# PowerSupply.net
KiCad netlist of a schematic drawn in Altium Designer
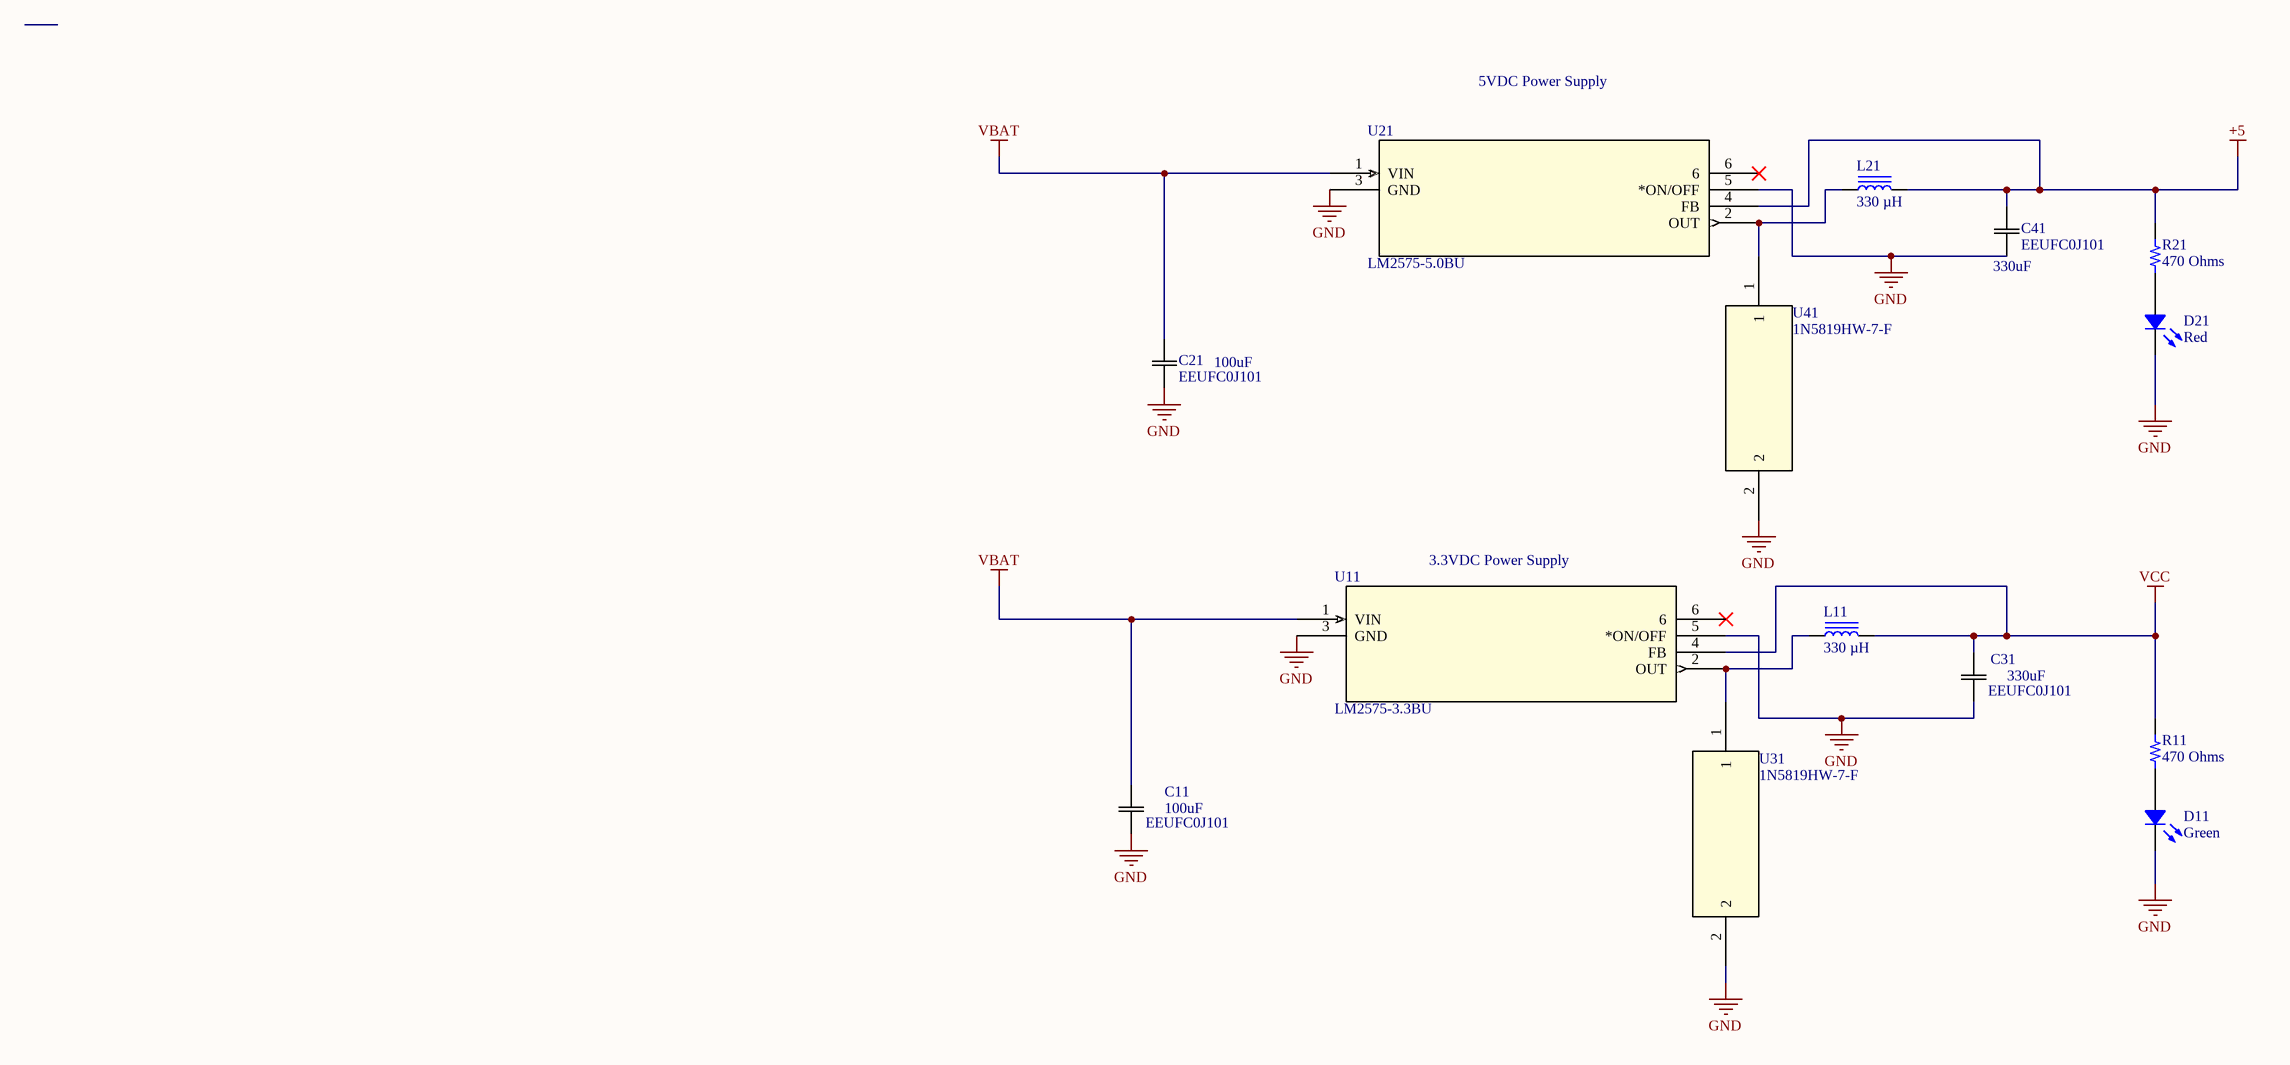
[diagram p0: PowerSupply.SchDoc]

(export (version "E")
  (design (tool "Eeschema 10.0.6"))
  (components
    (comp (ref "C11")
      (value "EEUFC0J101")
      (footprint "CAP_5 X 11_PAN")
      (description "No Description Available")
      (fields (field (name "ALTIUM_VALUE") "100uF"))
      (libsource (lib "EEUFC0J101") (part "EEUFC0J101"))
    )
    (comp (ref "C21")
      (value "EEUFC0J101")
      (footprint "CAP_5 X 11_PAN")
      (description "No Description Available")
      (fields (field (name "ALTIUM_VALUE") "100uF"))
      (libsource (lib "EEUFC0J101") (part "EEUFC0J101"))
    )
    (comp (ref "C31")
      (value "EEUFC0J101")
      (footprint "CAP_5 X 11_PAN")
      (description "No Description Available")
      (fields (field (name "ALTIUM_VALUE") "330uF"))
      (libsource (lib "EEUFC0J101") (part "EEUFC0J101"))
    )
    (comp (ref "C41")
      (value "EEUFC0J101")
      (footprint "CAP_5 X 11_PAN")
      (description "No Description Available")
      (fields (field (name "ALTIUM_VALUE") "330uF"))
      (libsource (lib "EEUFC0J101") (part "EEUFC0J101"))
    )
    (comp (ref "D11")
      (value "Green")
      (footprint "LED 1206_3216 GREEN")
      (description "LED GREEN 1206 SMD")
      (fields (field (name "PART NUMBER") "597-6322-107F") (field (name "MANUFACTURER") "Dialight"))
      (libsource (lib "Celestial Altium Library - altium_library") (part "LED"))
    )
    (comp (ref "D21")
      (value "Red")
      (footprint "LED 1206_3216 RED")
      (description "LED RED CLEAR 1206 SMD")
      (fields
        (field (name "PART NUMBER") "25-21/R6C-BR2S2B/2A")
        (field (name "MANUFACTURER") "Everlight Electronics Co Ltd")
      )
      (libsource (lib "Celestial Altium Library - altium_library") (part "LED"))
    )
    (comp (ref "L11")
      (value "330 µH")
      (footprint "BOURNS SRR1280")
      (description "FIXED IND 330UH 1.1A 600MOHM SMD")
      (fields (field (name "PART NUMBER") "SRR1280-331K") (field (name "MANUFACTURER") "Bourns Inc."))
      (libsource (lib "Celestial Altium Library - altium_library") (part "Inductor"))
    )
    (comp (ref "L21")
      (value "330 µH")
      (footprint "BOURNS SRR1280")
      (description "FIXED IND 330UH 1.1A 600MOHM SMD")
      (fields (field (name "PART NUMBER") "SRR1280-331K") (field (name "MANUFACTURER") "Bourns Inc."))
      (libsource (lib "Celestial Altium Library - altium_library") (part "Inductor"))
    )
    (comp (ref "R11")
      (value "470 Ohms")
      (footprint "RES 0805_2012")
      (description "RES 470 OHM 1% 1/4W 0805")
      (fields (field (name "PART NUMBER") "AC0805FR-7W470RL") (field (name "MANUFACTURER") "Yageo"))
      (libsource (lib "Celestial Altium Library - altium_library") (part "Resistor"))
    )
    (comp (ref "R21")
      (value "470 Ohms")
      (footprint "RES 0805_2012")
      (description "RES 470 OHM 1% 1/4W 0805")
      (fields (field (name "PART NUMBER") "AC0805FR-7W470RL") (field (name "MANUFACTURER") "Yageo"))
      (libsource (lib "Celestial Altium Library - altium_library") (part "Resistor"))
    )
    (comp (ref "U11")
      (value "LM2575-3.3BU")
      (footprint "TO-263-5_MCL")
      (description "No Description Available")
      (libsource (lib "LM2575-3P3BU") (part "LM2575-3.3BU"))
    )
    (comp (ref "U21")
      (value "LM2575-5.0BU")
      (footprint "TO-263-5_MCL-M")
      (description "No Description Available")
      (libsource (lib "LM2575-5P0BU") (part "LM2575-5.0BU"))
    )
    (comp (ref "U31")
      (value "1N5819HW-7-F")
      (footprint "1N5819HW-7-F_DIO")
      (description "No Description Available")
      (libsource (lib "1N5819HW-7-F") (part "1N5819HW-7-F"))
    )
    (comp (ref "U41")
      (value "1N5819HW-7-F")
      (footprint "1N5819HW-7-F_DIO")
      (description "No Description Available")
      (libsource (lib "1N5819HW-7-F") (part "1N5819HW-7-F"))
    )
  )
  (nets
    (net (code "1") (name "+5") (class "Default")
      (node (ref "C41") (pin "1") (pinfunction "1_1") (pintype "passive"))
      (node (ref "L21") (pin "2") (pinfunction "2_2") (pintype "passive"))
      (node (ref "R21") (pin "2") (pinfunction "2_2") (pintype "passive"))
      (node (ref "U21") (pin "4") (pinfunction "FB_4") (pintype "passive"))
    )
    (net (code "2") (name "GND") (class "Default")
      (node (ref "C11") (pin "2") (pinfunction "2_2") (pintype "passive"))
      (node (ref "C21") (pin "2") (pinfunction "2_2") (pintype "passive"))
      (node (ref "C31") (pin "2") (pinfunction "2_2") (pintype "passive"))
      (node (ref "C41") (pin "2") (pinfunction "2_2") (pintype "passive"))
      (node (ref "D11") (pin "2") (pinfunction "2_2") (pintype "passive"))
      (node (ref "D21") (pin "2") (pinfunction "2_2") (pintype "passive"))
      (node (ref "U11") (pin "3") (pinfunction "GND_3") (pintype "power_in"))
      (node (ref "U11") (pin "5") (pinfunction "*ON/OFF_5") (pintype "passive"))
      (node (ref "U21") (pin "3") (pinfunction "GND_3") (pintype "power_in"))
      (node (ref "U21") (pin "5") (pinfunction "*ON/OFF_5") (pintype "passive"))
      (node (ref "U31") (pin "2") (pinfunction "2_2") (pintype "passive"))
      (node (ref "U41") (pin "2") (pinfunction "2_2") (pintype "passive"))
    )
    (net (code "3") (name "Net-(D11-Pad1)") (class "Default")
      (node (ref "D11") (pin "1") (pinfunction "1_1") (pintype "passive"))
      (node (ref "R11") (pin "1") (pinfunction "1_1") (pintype "passive"))
    )
    (net (code "4") (name "Net-(D21-Pad1)") (class "Default")
      (node (ref "D21") (pin "1") (pinfunction "1_1") (pintype "passive"))
      (node (ref "R21") (pin "1") (pinfunction "1_1") (pintype "passive"))
    )
    (net (code "5") (name "Net-(U11-OUT)") (class "Default")
      (node (ref "L11") (pin "1") (pinfunction "1_1") (pintype "passive"))
      (node (ref "U11") (pin "2") (pinfunction "OUT_2") (pintype "output"))
      (node (ref "U31") (pin "1") (pinfunction "1_1") (pintype "passive"))
    )
    (net (code "6") (name "Net-(U21-OUT)") (class "Default")
      (node (ref "L21") (pin "1") (pinfunction "1_1") (pintype "passive"))
      (node (ref "U21") (pin "2") (pinfunction "OUT_2") (pintype "output"))
      (node (ref "U41") (pin "1") (pinfunction "1_1") (pintype "passive"))
    )
    (net (code "7") (name "VBAT") (class "Default")
      (node (ref "C11") (pin "1") (pinfunction "1_1") (pintype "passive"))
      (node (ref "C21") (pin "1") (pinfunction "1_1") (pintype "passive"))
      (node (ref "U11") (pin "1") (pinfunction "VIN_1") (pintype "input"))
      (node (ref "U21") (pin "1") (pinfunction "VIN_1") (pintype "input"))
    )
    (net (code "8") (name "VCC") (class "Default")
      (node (ref "C31") (pin "1") (pinfunction "1_1") (pintype "passive"))
      (node (ref "L11") (pin "2") (pinfunction "2_2") (pintype "passive"))
      (node (ref "R11") (pin "2") (pinfunction "2_2") (pintype "passive"))
      (node (ref "U11") (pin "4") (pinfunction "FB_4") (pintype "passive"))
    )
    (net (code "9") (name "unconnected-(U11-Pad6)") (class "Default")
      (node (ref "U11") (pin "6") (pinfunction "6_6") (pintype "passive+no_connect"))
    )
    (net (code "10") (name "unconnected-(U21-Pad6)") (class "Default")
      (node (ref "U21") (pin "6") (pinfunction "6_6") (pintype "passive+no_connect"))
    )
  )
)
